# servoDrv.net
KiCad netlist of a schematic drawn in EAGLE
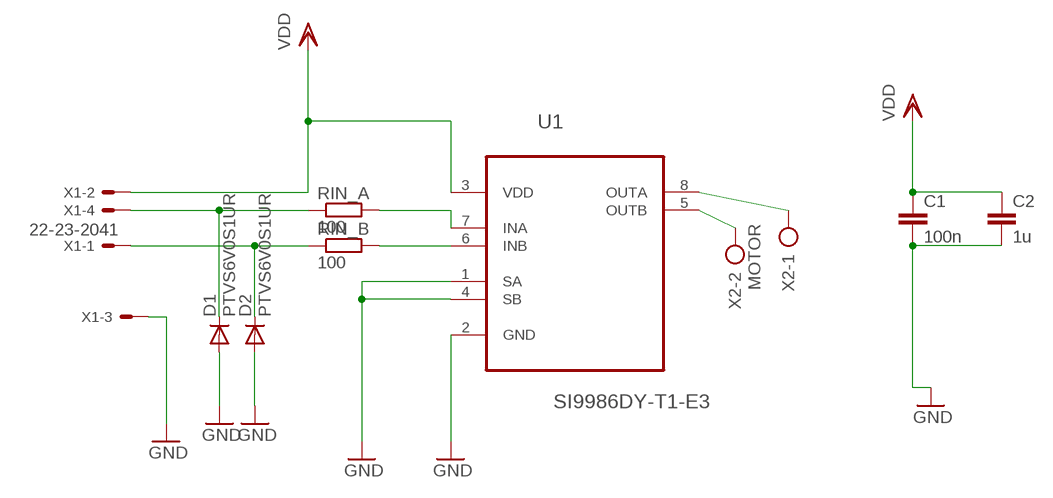
[diagram p0: schematic, sheet 1]

(export (version "E")
  (design (tool "Eeschema 10.0.6"))
  (components
    (comp (ref "C1")
      (value "100n")
      (footprint "eagle-import:C0805")
      (libsource (lib "eagle-import") (part "C-EUC0805"))
    )
    (comp (ref "C2")
      (value "1u")
      (footprint "eagle-import:C0805")
      (libsource (lib "eagle-import") (part "C-EUC0805"))
    )
    (comp (ref "D1")
      (value "PTVS6V0S1UR")
      (footprint "eagle-import:SOD123")
      (libsource (lib "eagle-import") (part "DIODE-SOD123"))
    )
    (comp (ref "D2")
      (value "PTVS6V0S1UR")
      (footprint "eagle-import:SOD123")
      (libsource (lib "eagle-import") (part "DIODE-SOD123"))
    )
    (comp (ref "RIN_A")
      (value "100")
      (footprint "eagle-import:0207_10")
      (libsource (lib "eagle-import") (part "R-EU_0207/10"))
    )
    (comp (ref "RIN_B")
      (value "100")
      (footprint "eagle-import:0207_10")
      (libsource (lib "eagle-import") (part "R-EU_0207/10"))
    )
    (comp (ref "U1")
      (value "SI9986DY-T1-E3")
      (footprint "eagle-import:SOIC127P600X175-8N")
      (libsource (lib "eagle-import") (part "SI9986DY-T1-E3"))
    )
    (comp (ref "X1")
      (value "22-23-2041")
      (footprint "eagle-import:22-23-2041")
      (fields (field (name "MF") "MOLEX"))
      (libsource (lib "eagle-import") (part "22-23-2041"))
    )
    (comp (ref "X2")
      (value "MOTOR")
      (footprint "eagle-import:AK500_2")
      (libsource (lib "eagle-import") (part "AK500/2"))
    )
  )
  (nets
    (net (code "1") (name "GND") (class "Default")
      (node (ref "C1") (pin "2") (pinfunction "2_2") (pintype "passive"))
      (node (ref "C2") (pin "2") (pinfunction "2_2") (pintype "passive"))
      (node (ref "D1") (pin "A") (pinfunction "A_A") (pintype "passive"))
      (node (ref "D2") (pin "A") (pinfunction "A_A") (pintype "passive"))
      (node (ref "U1") (pin "1") (pinfunction "SA_1") (pintype "input"))
      (node (ref "U1") (pin "2") (pinfunction "GND_2") (pintype "passive"))
      (node (ref "U1") (pin "4") (pinfunction "SB_4") (pintype "input"))
      (node (ref "X1") (pin "3") (pinfunction "S_3") (pintype "passive"))
    )
    (net (code "2") (name "Net-(U1-INA)") (class "Default")
      (node (ref "RIN_A") (pin "2") (pinfunction "2_2") (pintype "passive"))
      (node (ref "U1") (pin "7") (pinfunction "INA_7") (pintype "input"))
    )
    (net (code "3") (name "Net-(U1-INB)") (class "Default")
      (node (ref "RIN_B") (pin "2") (pinfunction "2_2") (pintype "passive"))
      (node (ref "U1") (pin "6") (pinfunction "INB_6") (pintype "input"))
    )
    (net (code "4") (name "Net-(U1-OUTA)") (class "Default")
      (node (ref "U1") (pin "8") (pinfunction "OUTA_8") (pintype "output"))
      (node (ref "X2") (pin "1") (pinfunction "KL_1") (pintype "passive"))
    )
    (net (code "5") (name "Net-(U1-OUTB)") (class "Default")
      (node (ref "U1") (pin "5") (pinfunction "OUTB_5") (pintype "output"))
      (node (ref "X2") (pin "2") (pinfunction "KL_2") (pintype "passive"))
    )
    (net (code "6") (name "Net-(X1A-S)") (class "Default")
      (node (ref "D2") (pin "C") (pinfunction "C_C") (pintype "passive"))
      (node (ref "RIN_B") (pin "1") (pinfunction "1_1") (pintype "passive"))
      (node (ref "X1") (pin "1") (pinfunction "S_1") (pintype "passive"))
    )
    (net (code "7") (name "Net-(X1D-S)") (class "Default")
      (node (ref "D1") (pin "C") (pinfunction "C_C") (pintype "passive"))
      (node (ref "RIN_A") (pin "1") (pinfunction "1_1") (pintype "passive"))
      (node (ref "X1") (pin "4") (pinfunction "S_4") (pintype "passive"))
    )
    (net (code "8") (name "VDD") (class "Default")
      (node (ref "C1") (pin "1") (pinfunction "1_1") (pintype "passive"))
      (node (ref "C2") (pin "1") (pinfunction "1_1") (pintype "passive"))
      (node (ref "U1") (pin "3") (pinfunction "VDD_3") (pintype "power_in"))
      (node (ref "X1") (pin "2") (pinfunction "S_2") (pintype "passive"))
    )
  )
)
